# LPFlasher.net
KiCad netlist of a schematic drawn in EAGLE
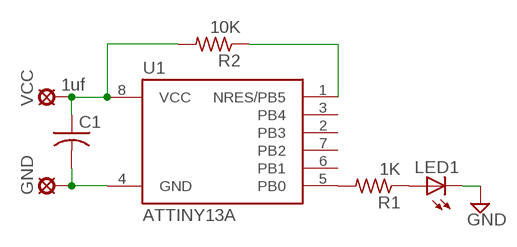
[diagram p0: schematic, sheet 1]

(export (version "E")
  (design (tool "Eeschema 10.0.6"))
  (components
    (comp (ref "C1")
      (value "1uf")
      (footprint "eagle-import:C025-024X044")
      (libsource (lib "eagle-import") (part "C-US025-024X044"))
    )
    (comp (ref "GND")
      (value "LSP13")
      (footprint "eagle-import:LSP13")
      (libsource (lib "eagle-import") (part "LSP13"))
    )
    (comp (ref "LED1")
      (value "LED5MM")
      (footprint "eagle-import:LED5MM")
      (libsource (lib "eagle-import") (part "LED5MM"))
    )
    (comp (ref "R1")
      (value "1K")
      (footprint "eagle-import:0204V")
      (libsource (lib "eagle-import") (part "R-US_0204/2V"))
    )
    (comp (ref "R2")
      (value "10K")
      (footprint "eagle-import:0204V")
      (libsource (lib "eagle-import") (part "R-US_0204/2V"))
    )
    (comp (ref "U1")
      (value "ATTINY13A")
      (footprint "eagle-import:PDIP08_300MIL")
      (libsource (lib "eagle-import") (part "ATTINY25P-"))
    )
    (comp (ref "VCC")
      (value "LSP13")
      (footprint "eagle-import:LSP13")
      (libsource (lib "eagle-import") (part "LSP13"))
    )
  )
  (nets
    (net (code "1") (name "GND") (class "Default")
      (node (ref "C1") (pin "2") (pinfunction "2_2") (pintype "passive"))
      (node (ref "GND") (pin "MP") (pinfunction "MP_MP") (pintype "passive"))
      (node (ref "LED1") (pin "K") (pinfunction "C_K") (pintype "passive"))
      (node (ref "U1") (pin "4") (pinfunction "GND_4") (pintype "power_in"))
    )
    (net (code "2") (name "Net-(LED1-PadA)") (class "Default")
      (node (ref "LED1") (pin "A") (pinfunction "A_A") (pintype "passive"))
      (node (ref "R1") (pin "1") (pinfunction "1_1") (pintype "passive"))
    )
    (net (code "3") (name "Net-(U1-NRES{slash}PB5)") (class "Default")
      (node (ref "R2") (pin "1") (pinfunction "1_1") (pintype "passive"))
      (node (ref "U1") (pin "1") (pinfunction "NRES/PB5_1") (pintype "bidirectional"))
    )
    (net (code "4") (name "Net-(U1-PB0)") (class "Default")
      (node (ref "R1") (pin "2") (pinfunction "2_2") (pintype "passive"))
      (node (ref "U1") (pin "5") (pinfunction "PB0_5") (pintype "bidirectional"))
    )
    (net (code "5") (name "Net-(U1-VCC)") (class "Default")
      (node (ref "C1") (pin "1") (pinfunction "1_1") (pintype "passive"))
      (node (ref "R2") (pin "2") (pinfunction "2_2") (pintype "passive"))
      (node (ref "U1") (pin "8") (pinfunction "VCC_8") (pintype "power_in"))
      (node (ref "VCC") (pin "MP") (pinfunction "MP_MP") (pintype "passive"))
    )
    (net (code "6") (name "unconnected-(U1-PB1-Pad6)") (class "Default")
      (node (ref "U1") (pin "6") (pinfunction "PB1_6") (pintype "bidirectional"))
    )
    (net (code "7") (name "unconnected-(U1-PB2-Pad7)") (class "Default")
      (node (ref "U1") (pin "7") (pinfunction "PB2_7") (pintype "bidirectional"))
    )
    (net (code "8") (name "unconnected-(U1-PB3-Pad2)") (class "Default")
      (node (ref "U1") (pin "2") (pinfunction "PB3_2") (pintype "bidirectional"))
    )
    (net (code "9") (name "unconnected-(U1-PB4-Pad3)") (class "Default")
      (node (ref "U1") (pin "3") (pinfunction "PB4_3") (pintype "bidirectional"))
    )
  )
)
